# Modulador_e_Demodulador_AM.net
KiCad netlist of a schematic drawn in EAGLE
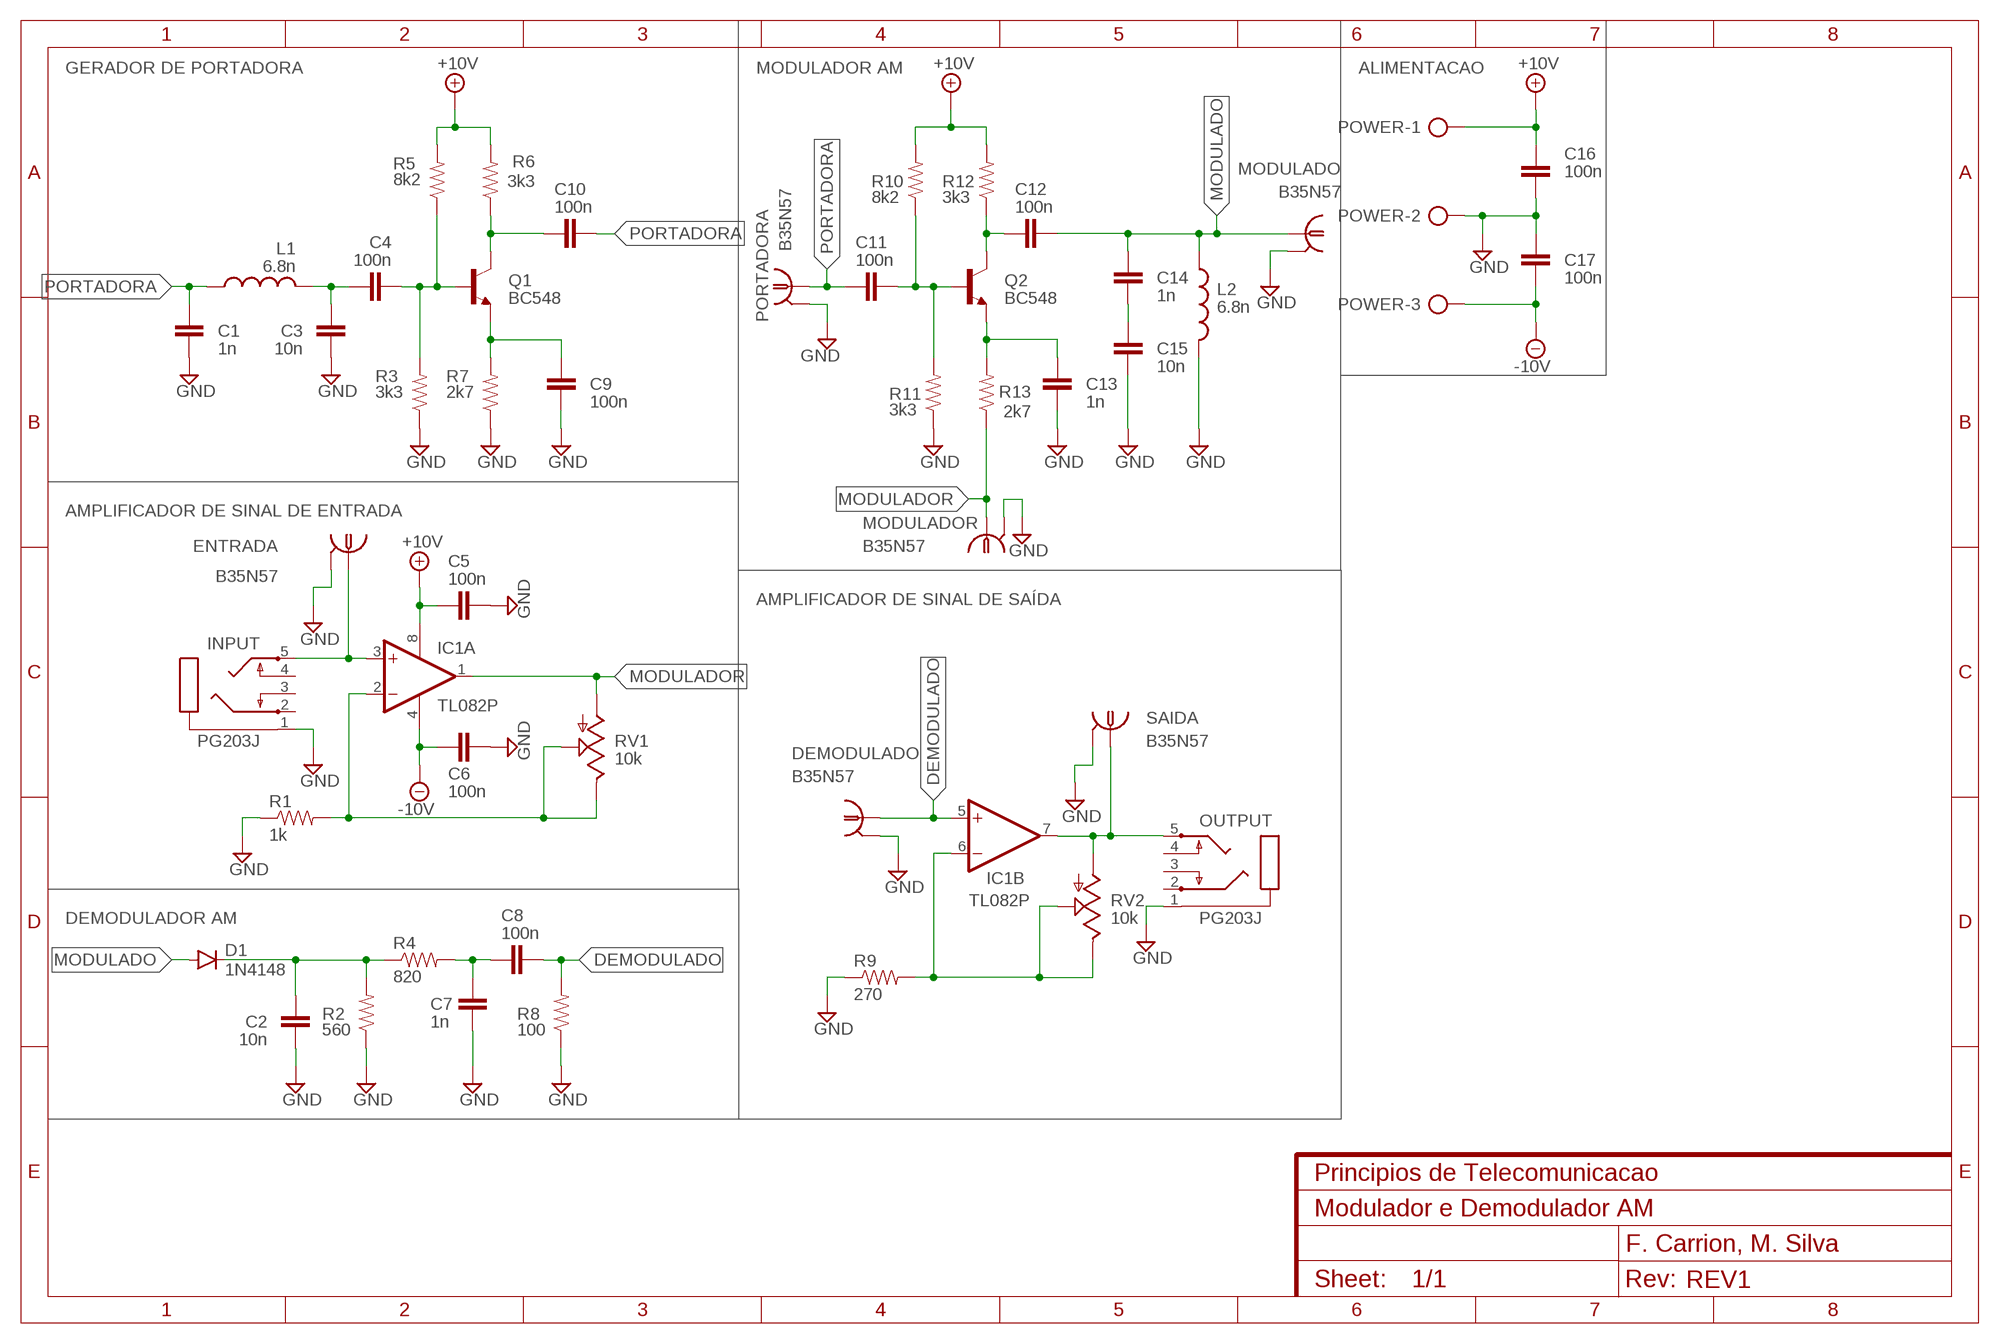
[diagram p0: schematic, sheet 1]

(export (version "E")
  (design (tool "Eeschema 10.0.6"))
  (components
    (comp (ref "C1")
      (value "1n")
      (footprint "eagle-import:CAP-PTH-SMALL2")
      (libsource (lib "eagle-import") (part "CAPPTH2"))
    )
    (comp (ref "C2")
      (value "10n")
      (footprint "eagle-import:CAP-PTH-SMALL2")
      (libsource (lib "eagle-import") (part "CAPPTH2"))
    )
    (comp (ref "C3")
      (value "10n")
      (footprint "eagle-import:CAP-PTH-SMALL2")
      (libsource (lib "eagle-import") (part "CAPPTH2"))
    )
    (comp (ref "C4")
      (value "100n")
      (footprint "eagle-import:CAP-PTH-SMALL2")
      (libsource (lib "eagle-import") (part "CAPPTH2"))
    )
    (comp (ref "C5")
      (value "100n")
      (footprint "eagle-import:CAP-PTH-SMALL2")
      (libsource (lib "eagle-import") (part "CAPPTH2"))
    )
    (comp (ref "C6")
      (value "100n")
      (footprint "eagle-import:CAP-PTH-SMALL2")
      (libsource (lib "eagle-import") (part "CAPPTH2"))
    )
    (comp (ref "C7")
      (value "1n")
      (footprint "eagle-import:CAP-PTH-SMALL2")
      (libsource (lib "eagle-import") (part "CAPPTH2"))
    )
    (comp (ref "C8")
      (value "100n")
      (footprint "eagle-import:CAP-PTH-SMALL2")
      (libsource (lib "eagle-import") (part "CAPPTH2"))
    )
    (comp (ref "C9")
      (value "100n")
      (footprint "eagle-import:CAP-PTH-SMALL2")
      (libsource (lib "eagle-import") (part "CAPPTH2"))
    )
    (comp (ref "C10")
      (value "100n")
      (footprint "eagle-import:CAP-PTH-SMALL2")
      (libsource (lib "eagle-import") (part "CAPPTH2"))
    )
    (comp (ref "C11")
      (value "100n")
      (footprint "eagle-import:CAP-PTH-SMALL2")
      (libsource (lib "eagle-import") (part "CAPPTH2"))
    )
    (comp (ref "C12")
      (value "100n")
      (footprint "eagle-import:CAP-PTH-SMALL2")
      (libsource (lib "eagle-import") (part "CAPPTH2"))
    )
    (comp (ref "C13")
      (value "1n")
      (footprint "eagle-import:CAP-PTH-SMALL2")
      (libsource (lib "eagle-import") (part "CAPPTH2"))
    )
    (comp (ref "C14")
      (value "1n")
      (footprint "eagle-import:CAP-PTH-SMALL2")
      (libsource (lib "eagle-import") (part "CAPPTH2"))
    )
    (comp (ref "C15")
      (value "10n")
      (footprint "eagle-import:CAP-PTH-SMALL2")
      (libsource (lib "eagle-import") (part "CAPPTH2"))
    )
    (comp (ref "C16")
      (value "100n")
      (footprint "eagle-import:CAP-PTH-SMALL2")
      (libsource (lib "eagle-import") (part "CAPPTH2"))
    )
    (comp (ref "C17")
      (value "100n")
      (footprint "eagle-import:CAP-PTH-SMALL2")
      (libsource (lib "eagle-import") (part "CAPPTH2"))
    )
    (comp (ref "D1")
      (value "1N4148")
      (footprint "eagle-import:DIODE-1N4148")
      (libsource (lib "eagle-import") (part "DIODE1N4148"))
    )
    (comp (ref "DEMODULADO")
      (value "B35N57")
      (footprint "eagle-import:B35N57")
      (libsource (lib "eagle-import") (part "B35N57"))
    )
    (comp (ref "ENTRADA")
      (value "B35N57")
      (footprint "eagle-import:B35N57")
      (libsource (lib "eagle-import") (part "B35N57"))
    )
    (comp (ref "IC1")
      (value "TL082P")
      (footprint "eagle-import:DIL08")
      (libsource (lib "eagle-import") (part "TL082P"))
    )
    (comp (ref "INPUT")
      (value "PG203J")
      (footprint "eagle-import:PG203J")
      (libsource (lib "eagle-import") (part "PG203J"))
    )
    (comp (ref "L1")
      (value "6.8n")
      (footprint "eagle-import:0207_10")
      (libsource (lib "eagle-import") (part "L-US0207/10"))
    )
    (comp (ref "L2")
      (value "6.8n")
      (footprint "eagle-import:0207_10")
      (libsource (lib "eagle-import") (part "L-US0207/10"))
    )
    (comp (ref "MODULADO")
      (value "B35N57")
      (footprint "eagle-import:B35N57")
      (libsource (lib "eagle-import") (part "B35N57"))
    )
    (comp (ref "MODULADOR")
      (value "B35N57")
      (footprint "eagle-import:B35N57")
      (libsource (lib "eagle-import") (part "B35N57"))
    )
    (comp (ref "OUTPUT")
      (value "PG203J")
      (footprint "eagle-import:PG203J")
      (libsource (lib "eagle-import") (part "PG203J"))
    )
    (comp (ref "PORTADORA")
      (value "B35N57")
      (footprint "eagle-import:B35N57")
      (libsource (lib "eagle-import") (part "B35N57"))
    )
    (comp (ref "POWER")
      (value "AK500/3-H")
      (footprint "eagle-import:AK500_3-H")
      (libsource (lib "eagle-import") (part "AK500/3-H"))
    )
    (comp (ref "Q1")
      (value "BC548")
      (footprint "eagle-import:TO92-EBC")
      (libsource (lib "eagle-import") (part "BC548"))
    )
    (comp (ref "Q2")
      (value "BC548")
      (footprint "eagle-import:TO92-EBC")
      (libsource (lib "eagle-import") (part "BC548"))
    )
    (comp (ref "R1")
      (value "1k")
      (footprint "eagle-import:AXIAL-0.3")
      (libsource (lib "eagle-import") (part "RESISTORAXIAL-0.3"))
    )
    (comp (ref "R2")
      (value "560")
      (footprint "eagle-import:AXIAL-0.3")
      (libsource (lib "eagle-import") (part "RESISTORAXIAL-0.3"))
    )
    (comp (ref "R3")
      (value "3k3")
      (footprint "eagle-import:AXIAL-0.3")
      (libsource (lib "eagle-import") (part "RESISTORAXIAL-0.3"))
    )
    (comp (ref "R4")
      (value "820")
      (footprint "eagle-import:AXIAL-0.3")
      (libsource (lib "eagle-import") (part "RESISTORAXIAL-0.3"))
    )
    (comp (ref "R5")
      (value "8k2")
      (footprint "eagle-import:AXIAL-0.3")
      (libsource (lib "eagle-import") (part "RESISTORAXIAL-0.3"))
    )
    (comp (ref "R6")
      (value "3k3")
      (footprint "eagle-import:AXIAL-0.3")
      (libsource (lib "eagle-import") (part "RESISTORAXIAL-0.3"))
    )
    (comp (ref "R7")
      (value "2k7")
      (footprint "eagle-import:AXIAL-0.3")
      (libsource (lib "eagle-import") (part "RESISTORAXIAL-0.3"))
    )
    (comp (ref "R8")
      (value "100")
      (footprint "eagle-import:AXIAL-0.3")
      (libsource (lib "eagle-import") (part "RESISTORAXIAL-0.3"))
    )
    (comp (ref "R9")
      (value "270")
      (footprint "eagle-import:AXIAL-0.3")
      (libsource (lib "eagle-import") (part "RESISTORAXIAL-0.3"))
    )
    (comp (ref "R10")
      (value "8k2")
      (footprint "eagle-import:AXIAL-0.3")
      (libsource (lib "eagle-import") (part "RESISTORAXIAL-0.3"))
    )
    (comp (ref "R11")
      (value "3k3")
      (footprint "eagle-import:AXIAL-0.3")
      (libsource (lib "eagle-import") (part "RESISTORAXIAL-0.3"))
    )
    (comp (ref "R12")
      (value "3k3")
      (footprint "eagle-import:AXIAL-0.3")
      (libsource (lib "eagle-import") (part "RESISTORAXIAL-0.3"))
    )
    (comp (ref "R13")
      (value "2k7")
      (footprint "eagle-import:AXIAL-0.3")
      (libsource (lib "eagle-import") (part "RESISTORAXIAL-0.3"))
    )
    (comp (ref "RV1")
      (value "10k")
      (footprint "eagle-import:POT_ALPHA_RV16AF-20")
      (libsource (lib "eagle-import") (part "POT-RV16AF-20"))
    )
    (comp (ref "RV2")
      (value "10k")
      (footprint "eagle-import:POT_ALPHA_RV16AF-20")
      (libsource (lib "eagle-import") (part "POT-RV16AF-20"))
    )
    (comp (ref "SAIDA")
      (value "B35N57")
      (footprint "eagle-import:B35N57")
      (libsource (lib "eagle-import") (part "B35N57"))
    )
  )
  (nets
    (net (code "1") (name "+10V") (class "Default")
      (node (ref "C16") (pin "1") (pinfunction "1_1") (pintype "passive"))
      (node (ref "C5") (pin "1") (pinfunction "1_1") (pintype "passive"))
      (node (ref "IC1") (pin "8") (pinfunction "V+_8") (pintype "power_in"))
      (node (ref "POWER") (pin "1") (pinfunction "KL_1") (pintype "passive"))
      (node (ref "R10") (pin "P$2") (pinfunction "2_P$2") (pintype "passive"))
      (node (ref "R12") (pin "P$2") (pinfunction "2_P$2") (pintype "passive"))
      (node (ref "R5") (pin "P$2") (pinfunction "2_P$2") (pintype "passive"))
      (node (ref "R6") (pin "P$2") (pinfunction "2_P$2") (pintype "passive"))
    )
    (net (code "2") (name "-10V") (class "Default")
      (node (ref "C17") (pin "2") (pinfunction "2_2") (pintype "passive"))
      (node (ref "C6") (pin "1") (pinfunction "1_1") (pintype "passive"))
      (node (ref "IC1") (pin "4") (pinfunction "V-_4") (pintype "power_in"))
      (node (ref "POWER") (pin "3") (pinfunction "KL_3") (pintype "passive"))
    )
    (net (code "3") (name "DEMODULADO") (class "Default")
      (node (ref "C8") (pin "2") (pinfunction "2_2") (pintype "passive"))
      (node (ref "DEMODULADO") (pin "1") (pinfunction "1_1") (pintype "passive"))
      (node (ref "IC1") (pin "5") (pinfunction "+IN_5") (pintype "input"))
      (node (ref "R8") (pin "P$2") (pinfunction "2_P$2") (pintype "passive"))
    )
    (net (code "4") (name "GND") (class "Default")
      (node (ref "C1") (pin "2") (pinfunction "2_2") (pintype "passive"))
      (node (ref "C13") (pin "2") (pinfunction "2_2") (pintype "passive"))
      (node (ref "C15") (pin "2") (pinfunction "2_2") (pintype "passive"))
      (node (ref "C16") (pin "2") (pinfunction "2_2") (pintype "passive"))
      (node (ref "C17") (pin "1") (pinfunction "1_1") (pintype "passive"))
      (node (ref "C2") (pin "2") (pinfunction "2_2") (pintype "passive"))
      (node (ref "C3") (pin "2") (pinfunction "2_2") (pintype "passive"))
      (node (ref "C5") (pin "2") (pinfunction "2_2") (pintype "passive"))
      (node (ref "C6") (pin "2") (pinfunction "2_2") (pintype "passive"))
      (node (ref "C7") (pin "2") (pinfunction "2_2") (pintype "passive"))
      (node (ref "C9") (pin "2") (pinfunction "2_2") (pintype "passive"))
      (node (ref "DEMODULADO") (pin "2") (pinfunction "2_2") (pintype "passive"))
      (node (ref "DEMODULADO") (pin "3") (pinfunction "2_3") (pintype "passive"))
      (node (ref "DEMODULADO") (pin "4") (pinfunction "2_4") (pintype "passive"))
      (node (ref "DEMODULADO") (pin "5") (pinfunction "2_5") (pintype "passive"))
      (node (ref "ENTRADA") (pin "2") (pinfunction "2_2") (pintype "passive"))
      (node (ref "ENTRADA") (pin "3") (pinfunction "2_3") (pintype "passive"))
      (node (ref "ENTRADA") (pin "4") (pinfunction "2_4") (pintype "passive"))
      (node (ref "ENTRADA") (pin "5") (pinfunction "2_5") (pintype "passive"))
      (node (ref "INPUT") (pin "1") (pinfunction "1_1") (pintype "passive"))
      (node (ref "L2") (pin "2") (pinfunction "2_2") (pintype "passive"))
      (node (ref "MODULADO") (pin "2") (pinfunction "2_2") (pintype "passive"))
      (node (ref "MODULADO") (pin "3") (pinfunction "2_3") (pintype "passive"))
      (node (ref "MODULADO") (pin "4") (pinfunction "2_4") (pintype "passive"))
      (node (ref "MODULADO") (pin "5") (pinfunction "2_5") (pintype "passive"))
      (node (ref "MODULADOR") (pin "2") (pinfunction "2_2") (pintype "passive"))
      (node (ref "MODULADOR") (pin "3") (pinfunction "2_3") (pintype "passive"))
      (node (ref "MODULADOR") (pin "4") (pinfunction "2_4") (pintype "passive"))
      (node (ref "MODULADOR") (pin "5") (pinfunction "2_5") (pintype "passive"))
      (node (ref "OUTPUT") (pin "1") (pinfunction "1_1") (pintype "passive"))
      (node (ref "PORTADORA") (pin "2") (pinfunction "2_2") (pintype "passive"))
      (node (ref "PORTADORA") (pin "3") (pinfunction "2_3") (pintype "passive"))
      (node (ref "PORTADORA") (pin "4") (pinfunction "2_4") (pintype "passive"))
      (node (ref "PORTADORA") (pin "5") (pinfunction "2_5") (pintype "passive"))
      (node (ref "POWER") (pin "2") (pinfunction "KL_2") (pintype "passive"))
      (node (ref "R1") (pin "P$1") (pinfunction "1_P$1") (pintype "passive"))
      (node (ref "R11") (pin "P$1") (pinfunction "1_P$1") (pintype "passive"))
      (node (ref "R2") (pin "P$1") (pinfunction "1_P$1") (pintype "passive"))
      (node (ref "R3") (pin "P$1") (pinfunction "1_P$1") (pintype "passive"))
      (node (ref "R7") (pin "P$1") (pinfunction "1_P$1") (pintype "passive"))
      (node (ref "R8") (pin "P$1") (pinfunction "1_P$1") (pintype "passive"))
      (node (ref "R9") (pin "P$1") (pinfunction "1_P$1") (pintype "passive"))
      (node (ref "SAIDA") (pin "2") (pinfunction "2_2") (pintype "passive"))
      (node (ref "SAIDA") (pin "3") (pinfunction "2_3") (pintype "passive"))
      (node (ref "SAIDA") (pin "4") (pinfunction "2_4") (pintype "passive"))
      (node (ref "SAIDA") (pin "5") (pinfunction "2_5") (pintype "passive"))
    )
    (net (code "5") (name "MODULADO") (class "Default")
      (node (ref "C12") (pin "2") (pinfunction "2_2") (pintype "passive"))
      (node (ref "C14") (pin "1") (pinfunction "1_1") (pintype "passive"))
      (node (ref "D1") (pin "A") (pinfunction "A_A") (pintype "passive"))
      (node (ref "L2") (pin "1") (pinfunction "1_1") (pintype "passive"))
      (node (ref "MODULADO") (pin "1") (pinfunction "1_1") (pintype "passive"))
    )
    (net (code "6") (name "MODULADOR") (class "Default")
      (node (ref "IC1") (pin "1") (pinfunction "OUT_1") (pintype "output"))
      (node (ref "MODULADOR") (pin "1") (pinfunction "1_1") (pintype "passive"))
      (node (ref "R13") (pin "P$1") (pinfunction "1_P$1") (pintype "passive"))
      (node (ref "RV1") (pin "1") (pinfunction "A_1") (pintype "passive"))
    )
    (net (code "7") (name "Net-(C3-Pad1)") (class "Default")
      (node (ref "C3") (pin "1") (pinfunction "1_1") (pintype "passive"))
      (node (ref "C4") (pin "1") (pinfunction "1_1") (pintype "passive"))
      (node (ref "L1") (pin "2") (pinfunction "2_2") (pintype "passive"))
    )
    (net (code "8") (name "Net-(C14-Pad2)") (class "Default")
      (node (ref "C14") (pin "2") (pinfunction "2_2") (pintype "passive"))
      (node (ref "C15") (pin "1") (pinfunction "1_1") (pintype "passive"))
    )
    (net (code "9") (name "Net-(IC1A-+IN)") (class "Default")
      (node (ref "ENTRADA") (pin "1") (pinfunction "1_1") (pintype "passive"))
      (node (ref "IC1") (pin "3") (pinfunction "+IN_3") (pintype "input"))
      (node (ref "INPUT") (pin "5") (pinfunction "5_5") (pintype "passive"))
    )
    (net (code "10") (name "Net-(IC1A--IN)") (class "Default")
      (node (ref "IC1") (pin "2") (pinfunction "-IN_2") (pintype "input"))
      (node (ref "R1") (pin "P$2") (pinfunction "2_P$2") (pintype "passive"))
      (node (ref "RV1") (pin "2") (pinfunction "S_2") (pintype "passive"))
      (node (ref "RV1") (pin "3") (pinfunction "E_3") (pintype "passive"))
    )
    (net (code "11") (name "Net-(IC1B--IN)") (class "Default")
      (node (ref "IC1") (pin "6") (pinfunction "-IN_6") (pintype "input"))
      (node (ref "R9") (pin "P$2") (pinfunction "2_P$2") (pintype "passive"))
      (node (ref "RV2") (pin "2") (pinfunction "S_2") (pintype "passive"))
      (node (ref "RV2") (pin "3") (pinfunction "E_3") (pintype "passive"))
    )
    (net (code "12") (name "Net-(IC1B-OUT)") (class "Default")
      (node (ref "IC1") (pin "7") (pinfunction "OUT_7") (pintype "output"))
      (node (ref "OUTPUT") (pin "5") (pinfunction "5_5") (pintype "passive"))
      (node (ref "RV2") (pin "1") (pinfunction "A_1") (pintype "passive"))
      (node (ref "SAIDA") (pin "1") (pinfunction "1_1") (pintype "passive"))
    )
    (net (code "13") (name "Net-(R2-2)") (class "Default")
      (node (ref "C2") (pin "1") (pinfunction "1_1") (pintype "passive"))
      (node (ref "D1") (pin "C") (pinfunction "C_C") (pintype "passive"))
      (node (ref "R2") (pin "P$2") (pinfunction "2_P$2") (pintype "passive"))
      (node (ref "R4") (pin "P$1") (pinfunction "1_P$1") (pintype "passive"))
    )
    (net (code "14") (name "Net-(R3-2)") (class "Default")
      (node (ref "C4") (pin "2") (pinfunction "2_2") (pintype "passive"))
      (node (ref "Q1") (pin "B") (pinfunction "B_B") (pintype "passive"))
      (node (ref "R3") (pin "P$2") (pinfunction "2_P$2") (pintype "passive"))
      (node (ref "R5") (pin "P$1") (pinfunction "1_P$1") (pintype "passive"))
    )
    (net (code "15") (name "Net-(R4-2)") (class "Default")
      (node (ref "C7") (pin "1") (pinfunction "1_1") (pintype "passive"))
      (node (ref "C8") (pin "1") (pinfunction "1_1") (pintype "passive"))
      (node (ref "R4") (pin "P$2") (pinfunction "2_P$2") (pintype "passive"))
    )
    (net (code "16") (name "Net-(R6-1)") (class "Default")
      (node (ref "C10") (pin "1") (pinfunction "1_1") (pintype "passive"))
      (node (ref "Q1") (pin "C") (pinfunction "C_C") (pintype "passive"))
      (node (ref "R6") (pin "P$1") (pinfunction "1_P$1") (pintype "passive"))
    )
    (net (code "17") (name "Net-(R7-2)") (class "Default")
      (node (ref "C9") (pin "1") (pinfunction "1_1") (pintype "passive"))
      (node (ref "Q1") (pin "E") (pinfunction "E_E") (pintype "passive"))
      (node (ref "R7") (pin "P$2") (pinfunction "2_P$2") (pintype "passive"))
    )
    (net (code "18") (name "Net-(R10-1)") (class "Default")
      (node (ref "C11") (pin "2") (pinfunction "2_2") (pintype "passive"))
      (node (ref "Q2") (pin "B") (pinfunction "B_B") (pintype "passive"))
      (node (ref "R10") (pin "P$1") (pinfunction "1_P$1") (pintype "passive"))
      (node (ref "R11") (pin "P$2") (pinfunction "2_P$2") (pintype "passive"))
    )
    (net (code "19") (name "Net-(R12-1)") (class "Default")
      (node (ref "C12") (pin "1") (pinfunction "1_1") (pintype "passive"))
      (node (ref "Q2") (pin "C") (pinfunction "C_C") (pintype "passive"))
      (node (ref "R12") (pin "P$1") (pinfunction "1_P$1") (pintype "passive"))
    )
    (net (code "20") (name "Net-(R13-2)") (class "Default")
      (node (ref "C13") (pin "1") (pinfunction "1_1") (pintype "passive"))
      (node (ref "Q2") (pin "E") (pinfunction "E_E") (pintype "passive"))
      (node (ref "R13") (pin "P$2") (pinfunction "2_P$2") (pintype "passive"))
    )
    (net (code "21") (name "PORTADORA") (class "Default")
      (node (ref "C1") (pin "1") (pinfunction "1_1") (pintype "passive"))
      (node (ref "C10") (pin "2") (pinfunction "2_2") (pintype "passive"))
      (node (ref "C11") (pin "1") (pinfunction "1_1") (pintype "passive"))
      (node (ref "L1") (pin "1") (pinfunction "1_1") (pintype "passive"))
      (node (ref "PORTADORA") (pin "1") (pinfunction "1_1") (pintype "passive"))
    )
    (net (code "22") (name "unconnected-(INPUT-Pad2)") (class "Default")
      (node (ref "INPUT") (pin "2") (pinfunction "2_2") (pintype "passive"))
    )
    (net (code "23") (name "unconnected-(INPUT-Pad3)") (class "Default")
      (node (ref "INPUT") (pin "3") (pinfunction "3_3") (pintype "passive"))
    )
    (net (code "24") (name "unconnected-(INPUT-Pad4)") (class "Default")
      (node (ref "INPUT") (pin "4") (pinfunction "4_4") (pintype "passive"))
    )
    (net (code "25") (name "unconnected-(OUTPUT-Pad2)") (class "Default")
      (node (ref "OUTPUT") (pin "2") (pinfunction "2_2") (pintype "passive"))
    )
    (net (code "26") (name "unconnected-(OUTPUT-Pad3)") (class "Default")
      (node (ref "OUTPUT") (pin "3") (pinfunction "3_3") (pintype "passive"))
    )
    (net (code "27") (name "unconnected-(OUTPUT-Pad4)") (class "Default")
      (node (ref "OUTPUT") (pin "4") (pinfunction "4_4") (pintype "passive"))
    )
  )
)
